# ControlBoard.net
KiCad netlist of a schematic drawn in Altium Designer
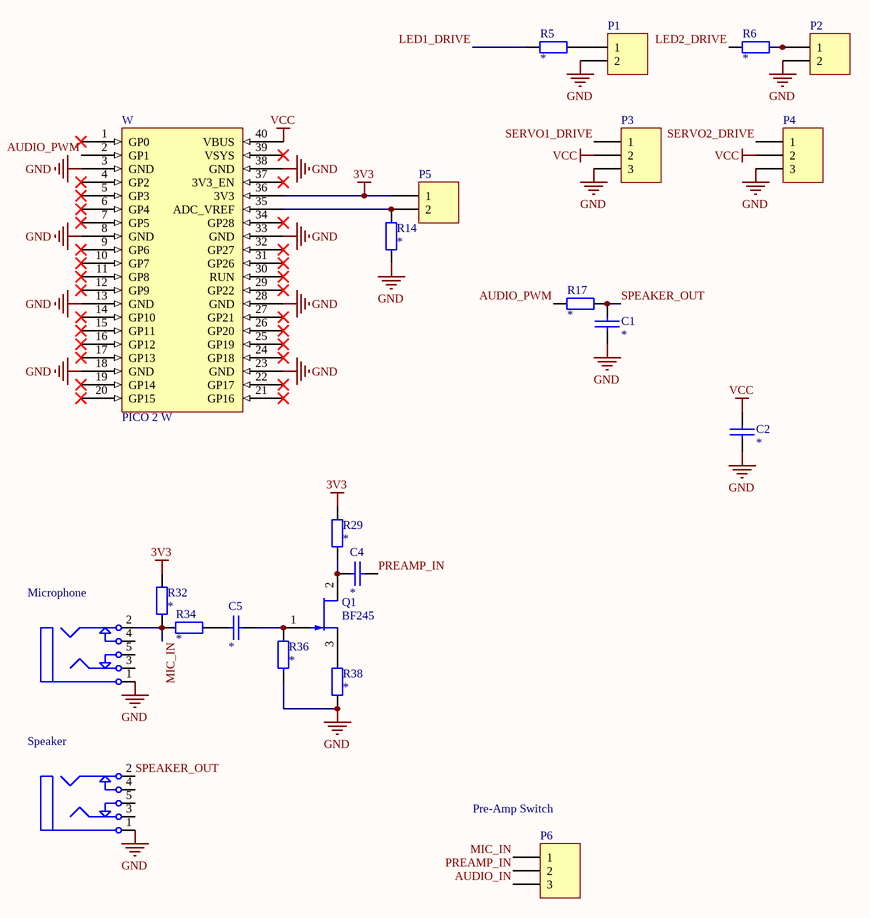
[diagram p0: ControlBoard.SchDoc]

(export (version "E")
  (design (tool "Eeschema 10.0.6"))
  (components
    (comp (ref "C1")
      (value "*")
      (footprint "ece-CC2012-0805")
      (description "SM capacitor")
      (libsource (lib "ece components") (part "CAP SM0805"))
    )
    (comp (ref "C2")
      (value "*")
      (footprint "ece-CC2012-0805")
      (description "SM capacitor")
      (libsource (lib "ece components") (part "CAP SM0805"))
    )
    (comp (ref "C4")
      (value "*")
      (footprint "ece-CC2012-0805")
      (description "SM capacitor")
      (libsource (lib "ece components") (part "CAP SM0805"))
    )
    (comp (ref "C5")
      (value "*")
      (footprint "ece-CC2012-0805")
      (description "SM capacitor")
      (libsource (lib "ece components") (part "CAP SM0805"))
    )
    (comp (ref "J1")
      (value "Phonejack Stereo")
      (footprint "ECE-phonejackStereo")
      (libsource (lib "ece components") (part "Phonejack-Stereo"))
    )
    (comp (ref "J2")
      (value "Phonejack Stereo")
      (footprint "ECE-phonejackStereo")
      (libsource (lib "ece components") (part "Phonejack-Stereo"))
    )
    (comp (ref "P1")
      (value "Header 2")
      (footprint "ece-HDR1X2")
      (description "Header, 2-Pin")
      (fields (field (name "PUBLISHER") "Altium Limited"))
      (libsource (lib "ece components") (part "Header 2"))
    )
    (comp (ref "P2")
      (value "Header 2")
      (footprint "ece-HDR1X2")
      (description "Header, 2-Pin")
      (fields (field (name "PUBLISHER") "Altium Limited"))
      (libsource (lib "ece components") (part "Header 2"))
    )
    (comp (ref "P3")
      (value "Header 3")
      (footprint "ece-HDR1X3")
      (description "Header, 3-Pin")
      (fields (field (name "PUBLISHER") "Altium Limited"))
      (libsource (lib "ece components") (part "Header 3"))
    )
    (comp (ref "P4")
      (value "Header 3")
      (footprint "ece-HDR1X3")
      (description "Header, 3-Pin")
      (fields (field (name "PUBLISHER") "Altium Limited"))
      (libsource (lib "ece components") (part "Header 3"))
    )
    (comp (ref "P5")
      (value "Header 2")
      (footprint "ece-HDR1X2")
      (description "Header, 2-Pin")
      (fields (field (name "PUBLISHER") "Altium Limited"))
      (libsource (lib "ece components") (part "Header 2"))
    )
    (comp (ref "P6")
      (value "Header 3")
      (footprint "ece-HDR1X3")
      (description "Header, 3-Pin")
      (fields (field (name "PUBLISHER") "Altium Limited"))
      (libsource (lib "ece components") (part "Header 3"))
    )
    (comp (ref "Q1")
      (value "BF245")
      (footprint "ece-TO-92")
      (description "N channel SFET")
      (libsource (lib "ece components") (part "BF245"))
    )
    (comp (ref "R5")
      (value "*")
      (footprint "RESC2012-0805SM")
      (description "SM resistor")
      (libsource (lib "") (part "Res SM 0805_1"))
    )
    (comp (ref "R6")
      (value "*")
      (footprint "RESC2012-0805SM")
      (description "SM resistor")
      (libsource (lib "") (part "Res SM 0805_1"))
    )
    (comp (ref "R14")
      (value "*")
      (footprint "RESC2012-0805SM")
      (description "SM resistor")
      (libsource (lib "") (part "Res SM 0805_2"))
    )
    (comp (ref "R17")
      (value "*")
      (footprint "RESC2012-0805SM")
      (description "SM resistor")
      (libsource (lib "") (part "Res SM 0805_3"))
    )
    (comp (ref "R29")
      (value "*")
      (footprint "RESC2012-0805SM")
      (description "SM resistor")
      (libsource (lib "") (part "Res SM 0805_2"))
    )
    (comp (ref "R32")
      (value "*")
      (footprint "RESC2012-0805SM")
      (description "SM resistor")
      (libsource (lib "ece components") (part "Res SM 0805"))
    )
    (comp (ref "R34")
      (value "*")
      (footprint "RESC2012-0805SM")
      (description "SM resistor")
      (libsource (lib "") (part "Res SM 0805_3"))
    )
    (comp (ref "R36")
      (value "*")
      (footprint "RESC2012-0805SM")
      (description "SM resistor")
      (libsource (lib "") (part "Res SM 0805_2"))
    )
    (comp (ref "R38")
      (value "*")
      (footprint "RESC2012-0805SM")
      (description "SM resistor")
      (libsource (lib "") (part "Res SM 0805_2"))
    )
    (comp (ref "W")
      (value "PICO 2 W")
      (footprint "DIP40")
      (description "The PICO 2 W throughhole symbol thing")
      (libsource (lib "stuff") (part "PICO 2 W-Symbol-1"))
    )
  )
  (nets
    (net (code "1") (name "/AUDIO_IN") (class "Default")
      (node (ref "P6") (pin "3") (pinfunction "3_3") (pintype "passive"))
    )
    (net (code "2") (name "/AUDIO_PWM") (class "Default")
      (node (ref "R17") (pin "2") (pinfunction "2_2") (pintype "passive"))
      (node (ref "W") (pin "2") (pinfunction "GP1_2") (pintype "input"))
    )
    (net (code "3") (name "/LED1_DRIVE") (class "Default")
      (node (ref "R5") (pin "1") (pinfunction "1_1") (pintype "passive"))
    )
    (net (code "4") (name "/LED2_DRIVE") (class "Default")
      (node (ref "R6") (pin "1") (pinfunction "1_1") (pintype "passive"))
    )
    (net (code "5") (name "/MIC_IN") (class "Default")
      (node (ref "J1") (pin "2") (pinfunction "2_2") (pintype "passive"))
      (node (ref "P6") (pin "1") (pinfunction "1_1") (pintype "passive"))
      (node (ref "R32") (pin "1") (pinfunction "1_1") (pintype "passive"))
      (node (ref "R34") (pin "2") (pinfunction "2_2") (pintype "passive"))
    )
    (net (code "6") (name "/PREAMP_IN") (class "Default")
      (node (ref "C4") (pin "2") (pinfunction "2_2") (pintype "passive"))
      (node (ref "P6") (pin "2") (pinfunction "2_2") (pintype "passive"))
    )
    (net (code "7") (name "/SERVO1_DRIVE") (class "Default")
      (node (ref "P3") (pin "1") (pinfunction "1_1") (pintype "passive"))
    )
    (net (code "8") (name "/SERVO2_DRIVE") (class "Default")
      (node (ref "P4") (pin "1") (pinfunction "1_1") (pintype "passive"))
    )
    (net (code "9") (name "/SPEAKER_OUT") (class "Default")
      (node (ref "C1") (pin "1") (pinfunction "1_1") (pintype "passive"))
      (node (ref "J2") (pin "2") (pinfunction "2_2") (pintype "passive"))
      (node (ref "R17") (pin "1") (pinfunction "1_1") (pintype "passive"))
    )
    (net (code "10") (name "3V3") (class "Default")
      (node (ref "P5") (pin "1") (pinfunction "1_1") (pintype "passive"))
      (node (ref "R29") (pin "1") (pinfunction "1_1") (pintype "passive"))
      (node (ref "R32") (pin "2") (pinfunction "2_2") (pintype "passive"))
      (node (ref "W") (pin "36") (pinfunction "3V3_36") (pintype "input"))
    )
    (net (code "11") (name "GND") (class "Default")
      (node (ref "C1") (pin "2") (pinfunction "2_2") (pintype "passive"))
      (node (ref "C2") (pin "2") (pinfunction "2_2") (pintype "passive"))
      (node (ref "J1") (pin "1") (pinfunction "1_1") (pintype "passive"))
      (node (ref "J2") (pin "1") (pinfunction "1_1") (pintype "passive"))
      (node (ref "P1") (pin "2") (pinfunction "2_2") (pintype "passive"))
      (node (ref "P2") (pin "2") (pinfunction "2_2") (pintype "passive"))
      (node (ref "P3") (pin "3") (pinfunction "3_3") (pintype "passive"))
      (node (ref "P4") (pin "3") (pinfunction "3_3") (pintype "passive"))
      (node (ref "R14") (pin "2") (pinfunction "2_2") (pintype "passive"))
      (node (ref "R36") (pin "2") (pinfunction "2_2") (pintype "passive"))
      (node (ref "R38") (pin "2") (pinfunction "2_2") (pintype "passive"))
      (node (ref "W") (pin "13") (pinfunction "GND_13") (pintype "input"))
      (node (ref "W") (pin "18") (pinfunction "GND_18") (pintype "input"))
      (node (ref "W") (pin "23") (pinfunction "GND_23") (pintype "input"))
      (node (ref "W") (pin "28") (pinfunction "GND_28") (pintype "input"))
      (node (ref "W") (pin "3") (pinfunction "GND_3") (pintype "input"))
      (node (ref "W") (pin "33") (pinfunction "GND_33") (pintype "input"))
      (node (ref "W") (pin "38") (pinfunction "GND_38") (pintype "input"))
      (node (ref "W") (pin "8") (pinfunction "GND_8") (pintype "input"))
    )
    (net (code "12") (name "Net-(C5-Pad1)") (class "Default")
      (node (ref "C5") (pin "1") (pinfunction "1_1") (pintype "passive"))
      (node (ref "R34") (pin "1") (pinfunction "1_1") (pintype "passive"))
    )
    (net (code "13") (name "Net-(P1-Pad1)") (class "Default")
      (node (ref "P1") (pin "1") (pinfunction "1_1") (pintype "passive"))
      (node (ref "R5") (pin "2") (pinfunction "2_2") (pintype "passive"))
    )
    (net (code "14") (name "Net-(P2-Pad1)") (class "Default")
      (node (ref "P2") (pin "1") (pinfunction "1_1") (pintype "passive"))
      (node (ref "R6") (pin "2") (pinfunction "2_2") (pintype "passive"))
    )
    (net (code "15") (name "Net-(Q1-D)") (class "Default")
      (node (ref "C4") (pin "1") (pinfunction "1_1") (pintype "passive"))
      (node (ref "Q1") (pin "2") (pinfunction "D_2") (pintype "passive"))
      (node (ref "R29") (pin "2") (pinfunction "2_2") (pintype "passive"))
    )
    (net (code "16") (name "Net-(Q1-G)") (class "Default")
      (node (ref "C5") (pin "2") (pinfunction "2_2") (pintype "passive"))
      (node (ref "Q1") (pin "1") (pinfunction "G_1") (pintype "passive"))
      (node (ref "R36") (pin "1") (pinfunction "1_1") (pintype "passive"))
    )
    (net (code "17") (name "Net-(Q1-S)") (class "Default")
      (node (ref "Q1") (pin "3") (pinfunction "S_3") (pintype "passive"))
      (node (ref "R38") (pin "1") (pinfunction "1_1") (pintype "passive"))
    )
    (net (code "18") (name "Net-(W-ADC_VREF)") (class "Default")
      (node (ref "P5") (pin "2") (pinfunction "2_2") (pintype "passive"))
      (node (ref "R14") (pin "1") (pinfunction "1_1") (pintype "passive"))
      (node (ref "W") (pin "35") (pinfunction "ADC_VREF_35") (pintype "input"))
    )
    (net (code "19") (name "VCC") (class "Default")
      (node (ref "C2") (pin "1") (pinfunction "1_1") (pintype "passive"))
      (node (ref "P3") (pin "2") (pinfunction "2_2") (pintype "passive"))
      (node (ref "P4") (pin "2") (pinfunction "2_2") (pintype "passive"))
      (node (ref "W") (pin "40") (pinfunction "VBUS_40") (pintype "input"))
    )
    (net (code "20") (name "unconnected-(J1-Pad3)") (class "Default")
      (node (ref "J1") (pin "3") (pinfunction "3_3") (pintype "passive"))
    )
    (net (code "21") (name "unconnected-(J1-Pad4)") (class "Default")
      (node (ref "J1") (pin "4") (pinfunction "4_4") (pintype "passive"))
    )
    (net (code "22") (name "unconnected-(J1-Pad5)") (class "Default")
      (node (ref "J1") (pin "5") (pinfunction "5_5") (pintype "passive"))
    )
    (net (code "23") (name "unconnected-(J2-Pad3)") (class "Default")
      (node (ref "J2") (pin "3") (pinfunction "3_3") (pintype "passive"))
    )
    (net (code "24") (name "unconnected-(J2-Pad4)") (class "Default")
      (node (ref "J2") (pin "4") (pinfunction "4_4") (pintype "passive"))
    )
    (net (code "25") (name "unconnected-(J2-Pad5)") (class "Default")
      (node (ref "J2") (pin "5") (pinfunction "5_5") (pintype "passive"))
    )
    (net (code "26") (name "unconnected-(W-3V3_EN-Pad37)") (class "Default")
      (node (ref "W") (pin "37") (pinfunction "3V3_EN_37") (pintype "input+no_connect"))
    )
    (net (code "27") (name "unconnected-(W-GP0-Pad1)") (class "Default")
      (node (ref "W") (pin "1") (pinfunction "GP0_1") (pintype "input+no_connect"))
    )
    (net (code "28") (name "unconnected-(W-GP2-Pad4)") (class "Default")
      (node (ref "W") (pin "4") (pinfunction "GP2_4") (pintype "input+no_connect"))
    )
    (net (code "29") (name "unconnected-(W-GP3-Pad5)") (class "Default")
      (node (ref "W") (pin "5") (pinfunction "GP3_5") (pintype "input+no_connect"))
    )
    (net (code "30") (name "unconnected-(W-GP4-Pad6)") (class "Default")
      (node (ref "W") (pin "6") (pinfunction "GP4_6") (pintype "input+no_connect"))
    )
    (net (code "31") (name "unconnected-(W-GP5-Pad7)") (class "Default")
      (node (ref "W") (pin "7") (pinfunction "GP5_7") (pintype "input+no_connect"))
    )
    (net (code "32") (name "unconnected-(W-GP6-Pad9)") (class "Default")
      (node (ref "W") (pin "9") (pinfunction "GP6_9") (pintype "input+no_connect"))
    )
    (net (code "33") (name "unconnected-(W-GP7-Pad10)") (class "Default")
      (node (ref "W") (pin "10") (pinfunction "GP7_10") (pintype "input+no_connect"))
    )
    (net (code "34") (name "unconnected-(W-GP8-Pad11)") (class "Default")
      (node (ref "W") (pin "11") (pinfunction "GP8_11") (pintype "input+no_connect"))
    )
    (net (code "35") (name "unconnected-(W-GP9-Pad12)") (class "Default")
      (node (ref "W") (pin "12") (pinfunction "GP9_12") (pintype "input+no_connect"))
    )
    (net (code "36") (name "unconnected-(W-GP10-Pad14)") (class "Default")
      (node (ref "W") (pin "14") (pinfunction "GP10_14") (pintype "input+no_connect"))
    )
    (net (code "37") (name "unconnected-(W-GP11-Pad15)") (class "Default")
      (node (ref "W") (pin "15") (pinfunction "GP11_15") (pintype "input+no_connect"))
    )
    (net (code "38") (name "unconnected-(W-GP12-Pad16)") (class "Default")
      (node (ref "W") (pin "16") (pinfunction "GP12_16") (pintype "input+no_connect"))
    )
    (net (code "39") (name "unconnected-(W-GP13-Pad17)") (class "Default")
      (node (ref "W") (pin "17") (pinfunction "GP13_17") (pintype "input+no_connect"))
    )
    (net (code "40") (name "unconnected-(W-GP14-Pad19)") (class "Default")
      (node (ref "W") (pin "19") (pinfunction "GP14_19") (pintype "input+no_connect"))
    )
    (net (code "41") (name "unconnected-(W-GP15-Pad20)") (class "Default")
      (node (ref "W") (pin "20") (pinfunction "GP15_20") (pintype "input+no_connect"))
    )
    (net (code "42") (name "unconnected-(W-GP16-Pad21)") (class "Default")
      (node (ref "W") (pin "21") (pinfunction "GP16_21") (pintype "input+no_connect"))
    )
    (net (code "43") (name "unconnected-(W-GP17-Pad22)") (class "Default")
      (node (ref "W") (pin "22") (pinfunction "GP17_22") (pintype "input+no_connect"))
    )
    (net (code "44") (name "unconnected-(W-GP18-Pad24)") (class "Default")
      (node (ref "W") (pin "24") (pinfunction "GP18_24") (pintype "input+no_connect"))
    )
    (net (code "45") (name "unconnected-(W-GP19-Pad25)") (class "Default")
      (node (ref "W") (pin "25") (pinfunction "GP19_25") (pintype "input+no_connect"))
    )
    (net (code "46") (name "unconnected-(W-GP20-Pad26)") (class "Default")
      (node (ref "W") (pin "26") (pinfunction "GP20_26") (pintype "input+no_connect"))
    )
    (net (code "47") (name "unconnected-(W-GP21-Pad27)") (class "Default")
      (node (ref "W") (pin "27") (pinfunction "GP21_27") (pintype "input+no_connect"))
    )
    (net (code "48") (name "unconnected-(W-GP22-Pad29)") (class "Default")
      (node (ref "W") (pin "29") (pinfunction "GP22_29") (pintype "input+no_connect"))
    )
    (net (code "49") (name "unconnected-(W-GP26-Pad31)") (class "Default")
      (node (ref "W") (pin "31") (pinfunction "GP26_31") (pintype "input+no_connect"))
    )
    (net (code "50") (name "unconnected-(W-GP27-Pad32)") (class "Default")
      (node (ref "W") (pin "32") (pinfunction "GP27_32") (pintype "input+no_connect"))
    )
    (net (code "51") (name "unconnected-(W-GP28-Pad34)") (class "Default")
      (node (ref "W") (pin "34") (pinfunction "GP28_34") (pintype "input+no_connect"))
    )
    (net (code "52") (name "unconnected-(W-RUN-Pad30)") (class "Default")
      (node (ref "W") (pin "30") (pinfunction "RUN_30") (pintype "input+no_connect"))
    )
    (net (code "53") (name "unconnected-(W-VSYS-Pad39)") (class "Default")
      (node (ref "W") (pin "39") (pinfunction "VSYS_39") (pintype "input+no_connect"))
    )
  )
)
